# Qwiic_USB_Bridge_SAMD21E.net
KiCad netlist of a schematic drawn in EAGLE
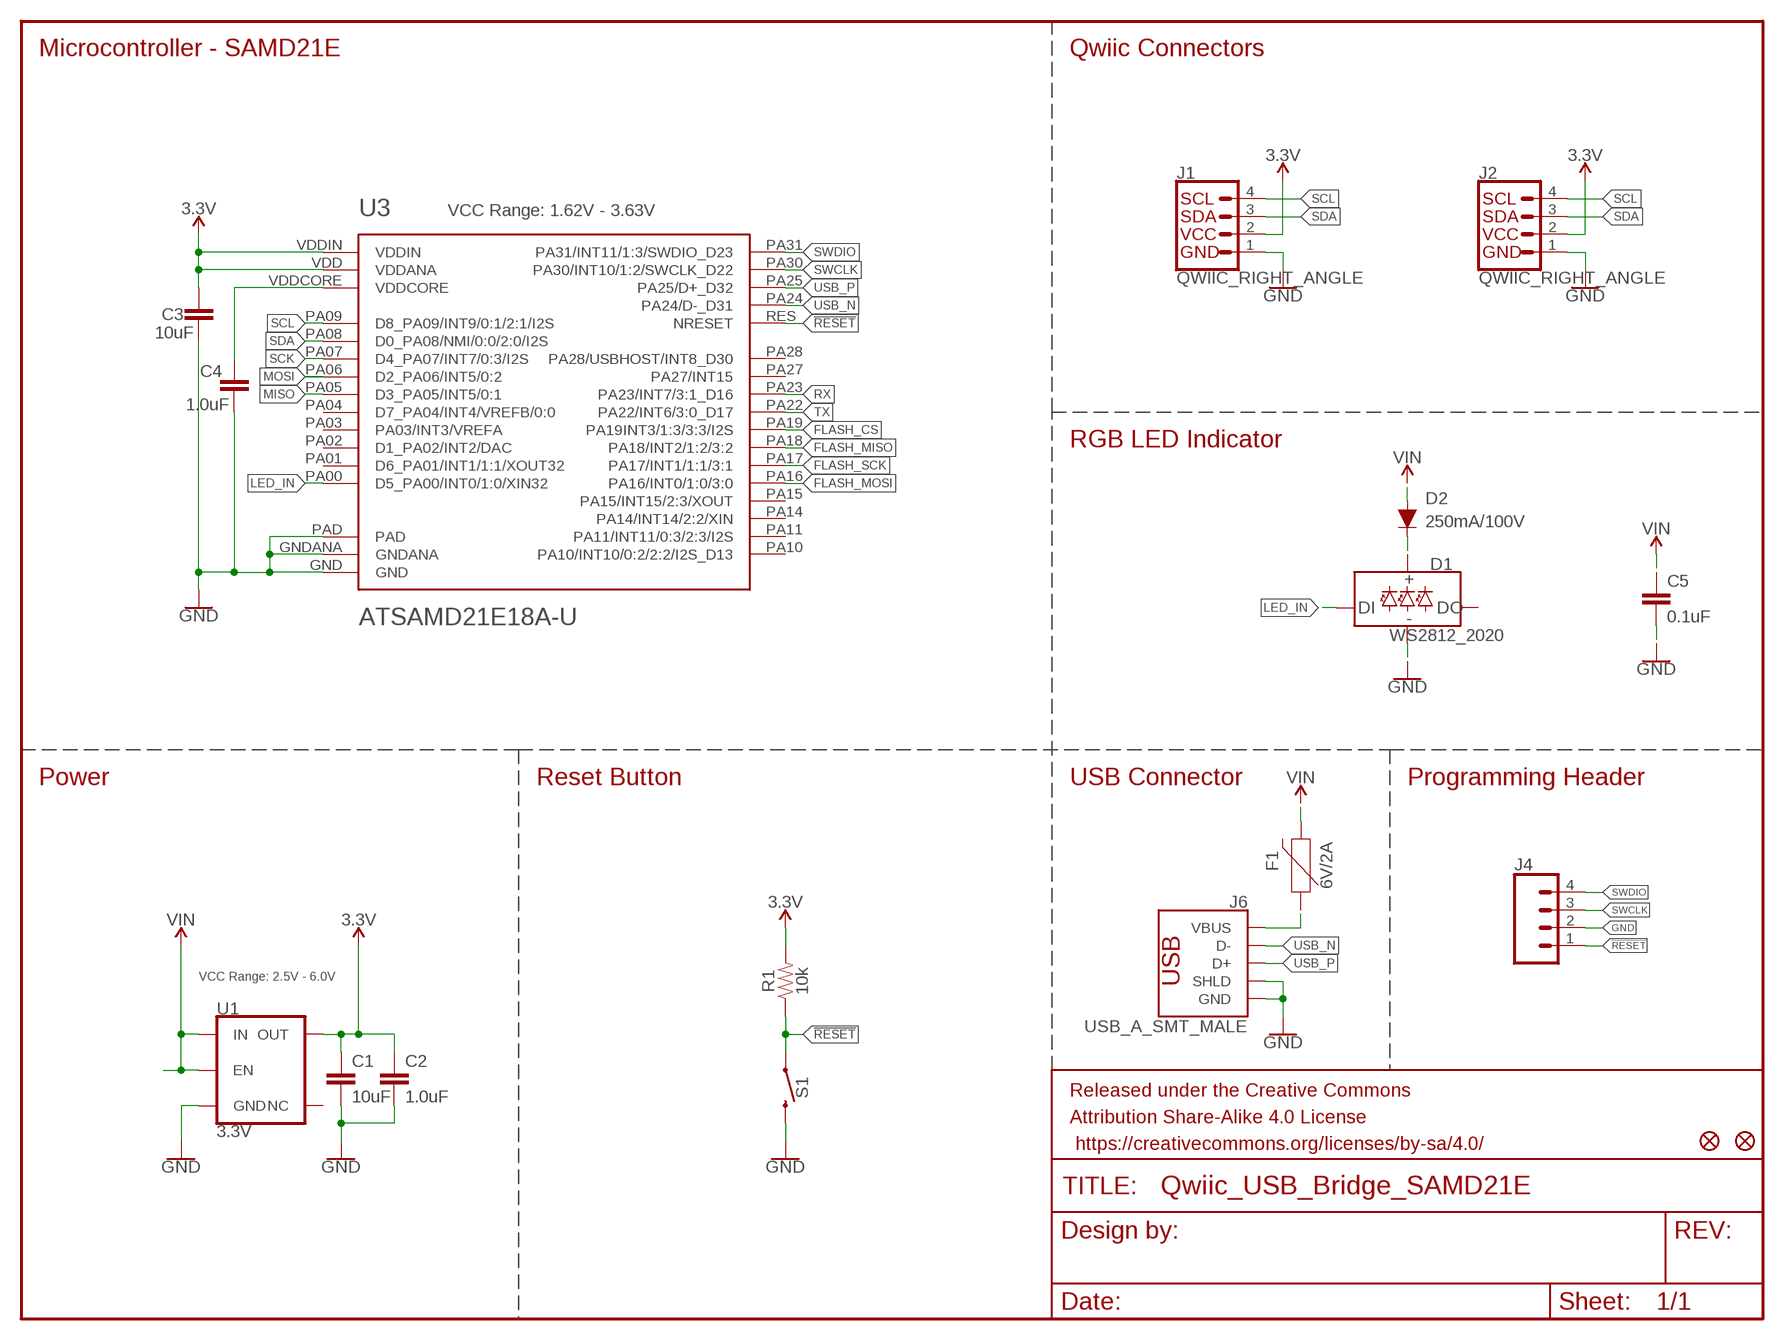
[diagram p0: schematic, sheet 1]

(export (version "E")
  (design (tool "Eeschema 10.0.6"))
  (components
    (comp (ref "C1")
      (value "10uF")
      (footprint "eagle-import:0603")
      (libsource (lib "eagle-import") (part "10UF-0603-6.3V-20%"))
    )
    (comp (ref "C2")
      (value "1.0uF")
      (footprint "eagle-import:0402")
      (libsource (lib "eagle-import") (part "1.0UF-0402-16V-10%"))
    )
    (comp (ref "C3")
      (value "10uF")
      (footprint "eagle-import:0603")
      (libsource (lib "eagle-import") (part "10UF-0603-6.3V-20%"))
    )
    (comp (ref "C4")
      (value "1.0uF")
      (footprint "eagle-import:0402")
      (libsource (lib "eagle-import") (part "1.0UF-0402-16V-10%"))
    )
    (comp (ref "C5")
      (value "0.1uF")
      (footprint "eagle-import:0603")
      (libsource (lib "eagle-import") (part "0.1UF-0603-25V-(+80/-20%)"))
    )
    (comp (ref "D1")
      (value "WS2812_2020")
      (footprint "eagle-import:WS2812-2020")
      (libsource (lib "eagle-import") (part "WS2812_2020"))
    )
    (comp (ref "D2")
      (value "250mA/100V")
      (footprint "eagle-import:SOD-323")
      (libsource (lib "eagle-import") (part "DIODE-BAS16J"))
    )
    (comp (ref "F1")
      (value "6V/2A")
      (footprint "eagle-import:1210")
      (libsource (lib "eagle-import") (part "PPTC_6V2A"))
    )
    (comp (ref "FD1")
      (value "FIDUCIALUFIDUCIAL")
      (footprint "eagle-import:FIDUCIAL-MICRO")
      (libsource (lib "eagle-import") (part "FIDUCIALUFIDUCIAL"))
    )
    (comp (ref "FD2")
      (value "FIDUCIALUFIDUCIAL")
      (footprint "eagle-import:FIDUCIAL-MICRO")
      (libsource (lib "eagle-import") (part "FIDUCIALUFIDUCIAL"))
    )
    (comp (ref "FRAME2")
      (value "FRAME-LETTER")
      (footprint "eagle-import:CREATIVE_COMMONS")
      (libsource (lib "eagle-import") (part "FRAME-LETTER"))
    )
    (comp (ref "J1")
      (value "QWIIC_RIGHT_ANGLE")
      (footprint "eagle-import:JST04_1MM_RA")
      (libsource (lib "eagle-import") (part "QWIIC_CONNECTORJS-1MM"))
    )
    (comp (ref "J2")
      (value "QWIIC_RIGHT_ANGLE")
      (footprint "eagle-import:JST04_1MM_RA")
      (libsource (lib "eagle-import") (part "QWIIC_CONNECTORJS-1MM"))
    )
    (comp (ref "J4")
      (value "CONN_041.27MM_NO_SILK")
      (footprint "eagle-import:1X04_1.27MM_NO_SILK")
      (libsource (lib "eagle-import") (part "CONN_041.27MM_NO_SILK"))
    )
    (comp (ref "J6")
      (value "USB_A_SMT_MALE")
      (footprint "eagle-import:USB-A-SMT-MALE")
      (libsource (lib "eagle-import") (part "USB_A_SMT_MALE"))
    )
    (comp (ref "R1")
      (value "10k")
      (footprint "eagle-import:0603")
      (libsource (lib "eagle-import") (part "10KOHM-0603-1/10W-1%"))
    )
    (comp (ref "S1")
      (value "MOMENTARY-SWITCH-SPST-SMD-6.0X3.5MM")
      (footprint "eagle-import:TACTILE_SWITCH_SMD_6.0X3.5MM")
      (libsource (lib "eagle-import") (part "MOMENTARY-SWITCH-SPST-SMD-6.0X3.5MM"))
    )
    (comp (ref "U1")
      (value "3.3V")
      (footprint "eagle-import:SOT23-5")
      (libsource (lib "eagle-import") (part "V_REG_AP2112K-3.3V"))
    )
    (comp (ref "U3")
      (value "ATSAMD21E18A-U")
      (footprint "eagle-import:QFN-32_SAMD")
      (libsource (lib "eagle-import") (part "ATSAMD21E18A-U"))
    )
  )
  (nets
    (net (code "1") (name "/~{RESET}") (class "Default")
      (node (ref "J4") (pin "1") (pinfunction "1_1") (pintype "passive"))
      (node (ref "R1") (pin "1") (pinfunction "1_1") (pintype "passive"))
      (node (ref "S1") (pin "1") (pinfunction "1_1") (pintype "passive"))
      (node (ref "U3") (pin "RES") (pinfunction "NRESET_RES") (pintype "bidirectional"))
    )
    (net (code "2") (name "3.3V") (class "Default")
      (node (ref "C1") (pin "1") (pinfunction "1_1") (pintype "passive"))
      (node (ref "C2") (pin "1") (pinfunction "1_1") (pintype "passive"))
      (node (ref "C3") (pin "1") (pinfunction "1_1") (pintype "passive"))
      (node (ref "J1") (pin "2") (pinfunction "2_2") (pintype "power_in"))
      (node (ref "J2") (pin "2") (pinfunction "2_2") (pintype "power_in"))
      (node (ref "R1") (pin "2") (pinfunction "2_2") (pintype "passive"))
      (node (ref "U1") (pin "5") (pinfunction "OUT_5") (pintype "passive"))
      (node (ref "U3") (pin "VDD") (pinfunction "VDDANA_VDD") (pintype "power_in"))
      (node (ref "U3") (pin "VDDIN") (pinfunction "VDDIN_VDDIN") (pintype "power_in"))
    )
    (net (code "3") (name "FLASH_CS") (class "Default")
      (node (ref "U3") (pin "PA19") (pinfunction "PA19INT3/1:3/3:3/I2S_PA19") (pintype "bidirectional"))
    )
    (net (code "4") (name "FLASH_MISO") (class "Default")
      (node (ref "U3") (pin "PA18") (pinfunction "PA18/INT2/1:2/3:2_PA18") (pintype "bidirectional"))
    )
    (net (code "5") (name "FLASH_MOSI") (class "Default")
      (node (ref "U3") (pin "PA16") (pinfunction "PA16/INT0/1:0/3:0_PA16") (pintype "bidirectional"))
    )
    (net (code "6") (name "FLASH_SCK") (class "Default")
      (node (ref "U3") (pin "PA17") (pinfunction "PA17/INT1/1:1/3:1_PA17") (pintype "bidirectional"))
    )
    (net (code "7") (name "GND") (class "Default")
      (node (ref "C1") (pin "2") (pinfunction "2_2") (pintype "passive"))
      (node (ref "C2") (pin "2") (pinfunction "2_2") (pintype "passive"))
      (node (ref "C3") (pin "2") (pinfunction "2_2") (pintype "passive"))
      (node (ref "C4") (pin "1") (pinfunction "1_1") (pintype "passive"))
      (node (ref "C5") (pin "2") (pinfunction "2_2") (pintype "passive"))
      (node (ref "D1") (pin "GND") (pinfunction "GND_GND") (pintype "bidirectional"))
      (node (ref "J1") (pin "1") (pinfunction "1_1") (pintype "power_in"))
      (node (ref "J2") (pin "1") (pinfunction "1_1") (pintype "power_in"))
      (node (ref "J4") (pin "2") (pinfunction "2_2") (pintype "passive"))
      (node (ref "J6") (pin "GND1") (pinfunction "GND_GND1") (pintype "power_in"))
      (node (ref "J6") (pin "SHLD1") (pinfunction "SHLD_SHLD1") (pintype "bidirectional"))
      (node (ref "J6") (pin "SHLD2") (pinfunction "SHLD_SHLD2") (pintype "bidirectional"))
      (node (ref "S1") (pin "2") (pinfunction "2_2") (pintype "passive"))
      (node (ref "U1") (pin "2") (pinfunction "GND_2") (pintype "input"))
      (node (ref "U3") (pin "GND") (pinfunction "GND_GND") (pintype "power_in"))
      (node (ref "U3") (pin "GNDANA") (pinfunction "GNDANA_GNDANA") (pintype "power_in"))
      (node (ref "U3") (pin "PAD") (pinfunction "PAD_PAD") (pintype "power_in"))
    )
    (net (code "8") (name "LED_IN") (class "Default")
      (node (ref "D1") (pin "DI") (pinfunction "DI_DI") (pintype "bidirectional"))
      (node (ref "U3") (pin "PA00") (pinfunction "D5_PA00/INT0/1:0/XIN32_PA00") (pintype "bidirectional"))
    )
    (net (code "9") (name "MISO") (class "Default")
      (node (ref "U3") (pin "PA05") (pinfunction "D3_PA05/INT5/0:1_PA05") (pintype "bidirectional"))
    )
    (net (code "10") (name "MOSI") (class "Default")
      (node (ref "U3") (pin "PA06") (pinfunction "D2_PA06/INT5/0:2_PA06") (pintype "bidirectional"))
    )
    (net (code "11") (name "Net-(C4-Pad2)") (class "Default")
      (node (ref "C4") (pin "2") (pinfunction "2_2") (pintype "passive"))
      (node (ref "U3") (pin "VDDCORE") (pinfunction "VDDCORE_VDDCORE") (pintype "power_in"))
    )
    (net (code "12") (name "Net-(D1-PadVCC)") (class "Default")
      (node (ref "D1") (pin "VCC") (pinfunction "VCC_VCC") (pintype "bidirectional"))
      (node (ref "D2") (pin "C") (pinfunction "C_C") (pintype "passive"))
    )
    (net (code "13") (name "Net-(J6-VBUS)") (class "Default")
      (node (ref "F1") (pin "1") (pinfunction "1_1") (pintype "bidirectional"))
      (node (ref "J6") (pin "VBUS1") (pinfunction "VBUS_VBUS1") (pintype "power_in"))
    )
    (net (code "14") (name "RX") (class "Default")
      (node (ref "U3") (pin "PA23") (pinfunction "PA23/INT7/3:1_D16_PA23") (pintype "bidirectional"))
    )
    (net (code "15") (name "SCK") (class "Default")
      (node (ref "U3") (pin "PA07") (pinfunction "D4_PA07/INT7/0:3/I2S_PA07") (pintype "bidirectional"))
    )
    (net (code "16") (name "SCL") (class "Default")
      (node (ref "J1") (pin "4") (pinfunction "4_4") (pintype "passive"))
      (node (ref "J2") (pin "4") (pinfunction "4_4") (pintype "passive"))
      (node (ref "U3") (pin "PA09") (pinfunction "D8_PA09/INT9/0:1/2:1/I2S_PA09") (pintype "bidirectional"))
    )
    (net (code "17") (name "SDA") (class "Default")
      (node (ref "J1") (pin "3") (pinfunction "3_3") (pintype "passive"))
      (node (ref "J2") (pin "3") (pinfunction "3_3") (pintype "passive"))
      (node (ref "U3") (pin "PA08") (pinfunction "D0_PA08/NMI/0:0/2:0/I2S_PA08") (pintype "bidirectional"))
    )
    (net (code "18") (name "SWCLK") (class "Default")
      (node (ref "J4") (pin "3") (pinfunction "3_3") (pintype "passive"))
      (node (ref "U3") (pin "PA30") (pinfunction "PA30/INT10/1:2/SWCLK_D22_PA30") (pintype "bidirectional"))
    )
    (net (code "19") (name "SWDIO") (class "Default")
      (node (ref "J4") (pin "4") (pinfunction "4_4") (pintype "passive"))
      (node (ref "U3") (pin "PA31") (pinfunction "PA31/INT11/1:3/SWDIO_D23_PA31") (pintype "bidirectional"))
    )
    (net (code "20") (name "TX") (class "Default")
      (node (ref "U3") (pin "PA22") (pinfunction "PA22/INT6/3:0_D17_PA22") (pintype "bidirectional"))
    )
    (net (code "21") (name "USB_N") (class "Default")
      (node (ref "J6") (pin "D-1") (pinfunction "D-_D-1") (pintype "bidirectional"))
      (node (ref "U3") (pin "PA24") (pinfunction "PA24/D-_D31_PA24") (pintype "bidirectional"))
    )
    (net (code "22") (name "USB_P") (class "Default")
      (node (ref "J6") (pin "D+1") (pinfunction "D+_D+1") (pintype "bidirectional"))
      (node (ref "U3") (pin "PA25") (pinfunction "PA25/D+_D32_PA25") (pintype "bidirectional"))
    )
    (net (code "23") (name "VIN") (class "Default")
      (node (ref "C5") (pin "1") (pinfunction "1_1") (pintype "passive"))
      (node (ref "D2") (pin "A") (pinfunction "A_A") (pintype "passive"))
      (node (ref "F1") (pin "2") (pinfunction "2_2") (pintype "bidirectional"))
      (node (ref "U1") (pin "1") (pinfunction "IN_1") (pintype "input"))
      (node (ref "U1") (pin "3") (pinfunction "EN_3") (pintype "input"))
    )
    (net (code "24") (name "unconnected-(D1-PadDO)") (class "Default")
      (node (ref "D1") (pin "DO") (pinfunction "DO_DO") (pintype "bidirectional"))
    )
    (net (code "25") (name "unconnected-(U1-NC-Pad4)") (class "Default")
      (node (ref "U1") (pin "4") (pinfunction "NC_4") (pintype "no_connect"))
    )
    (net (code "26") (name "unconnected-(U3-D1_PA02{slash}INT2{slash}DAC-PadPA02)") (class "Default")
      (node (ref "U3") (pin "PA02") (pinfunction "D1_PA02/INT2/DAC_PA02") (pintype "bidirectional"))
    )
    (net (code "27") (name "unconnected-(U3-D6_PA01{slash}INT1{slash}1:1{slash}XOUT32-PadPA01)") (class "Default")
      (node (ref "U3") (pin "PA01") (pinfunction "D6_PA01/INT1/1:1/XOUT32_PA01") (pintype "bidirectional"))
    )
    (net (code "28") (name "unconnected-(U3-D7_PA04{slash}INT4{slash}VREFB{slash}0:0-PadPA04)") (class "Default")
      (node (ref "U3") (pin "PA04") (pinfunction "D7_PA04/INT4/VREFB/0:0_PA04") (pintype "bidirectional"))
    )
    (net (code "29") (name "unconnected-(U3-PA03{slash}INT3{slash}VREFA-PadPA03)") (class "Default")
      (node (ref "U3") (pin "PA03") (pinfunction "PA03/INT3/VREFA_PA03") (pintype "bidirectional"))
    )
    (net (code "30") (name "unconnected-(U3-PA10{slash}INT10{slash}0:2{slash}2:2{slash}I2S_D13-PadPA10)") (class "Default")
      (node (ref "U3") (pin "PA10") (pinfunction "PA10/INT10/0:2/2:2/I2S_D13_PA10") (pintype "bidirectional"))
    )
    (net (code "31") (name "unconnected-(U3-PA11{slash}INT11{slash}0:3{slash}2:3{slash}I2S-PadPA11)") (class "Default")
      (node (ref "U3") (pin "PA11") (pinfunction "PA11/INT11/0:3/2:3/I2S_PA11") (pintype "bidirectional"))
    )
    (net (code "32") (name "unconnected-(U3-PA14{slash}INT14{slash}2:2{slash}XIN-PadPA14)") (class "Default")
      (node (ref "U3") (pin "PA14") (pinfunction "PA14/INT14/2:2/XIN_PA14") (pintype "bidirectional"))
    )
    (net (code "33") (name "unconnected-(U3-PA15{slash}INT15{slash}2:3{slash}XOUT-PadPA15)") (class "Default")
      (node (ref "U3") (pin "PA15") (pinfunction "PA15/INT15/2:3/XOUT_PA15") (pintype "bidirectional"))
    )
    (net (code "34") (name "unconnected-(U3-PA27{slash}INT15-PadPA27)") (class "Default")
      (node (ref "U3") (pin "PA27") (pinfunction "PA27/INT15_PA27") (pintype "bidirectional"))
    )
    (net (code "35") (name "unconnected-(U3-PA28{slash}USBHOST{slash}INT8_D30-PadPA28)") (class "Default")
      (node (ref "U3") (pin "PA28") (pinfunction "PA28/USBHOST/INT8_D30_PA28") (pintype "bidirectional"))
    )
  )
)
